# freesoc_sparkfun.net
KiCad netlist of a schematic drawn in EAGLE
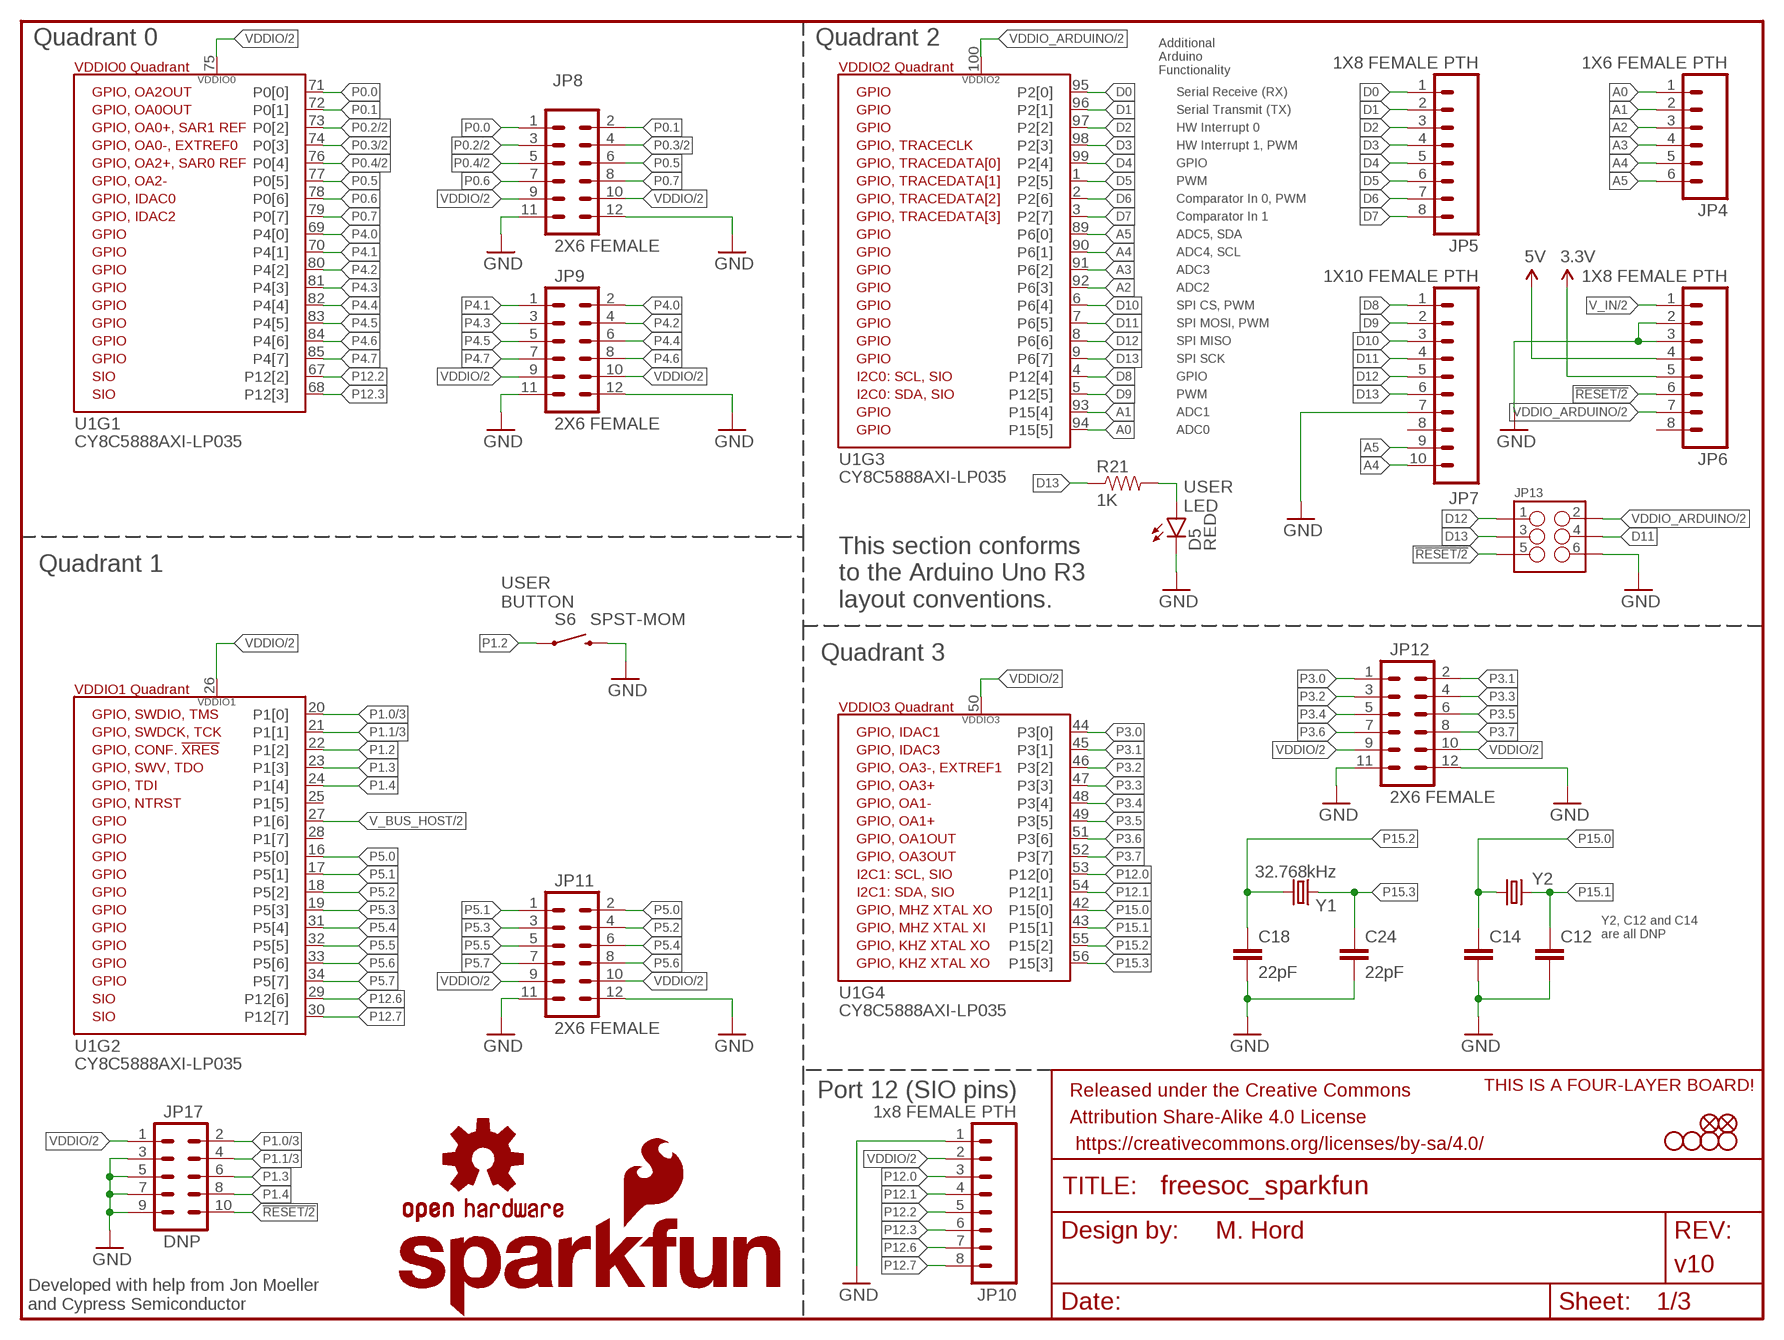
[diagram p0: schematic, sheet 1]
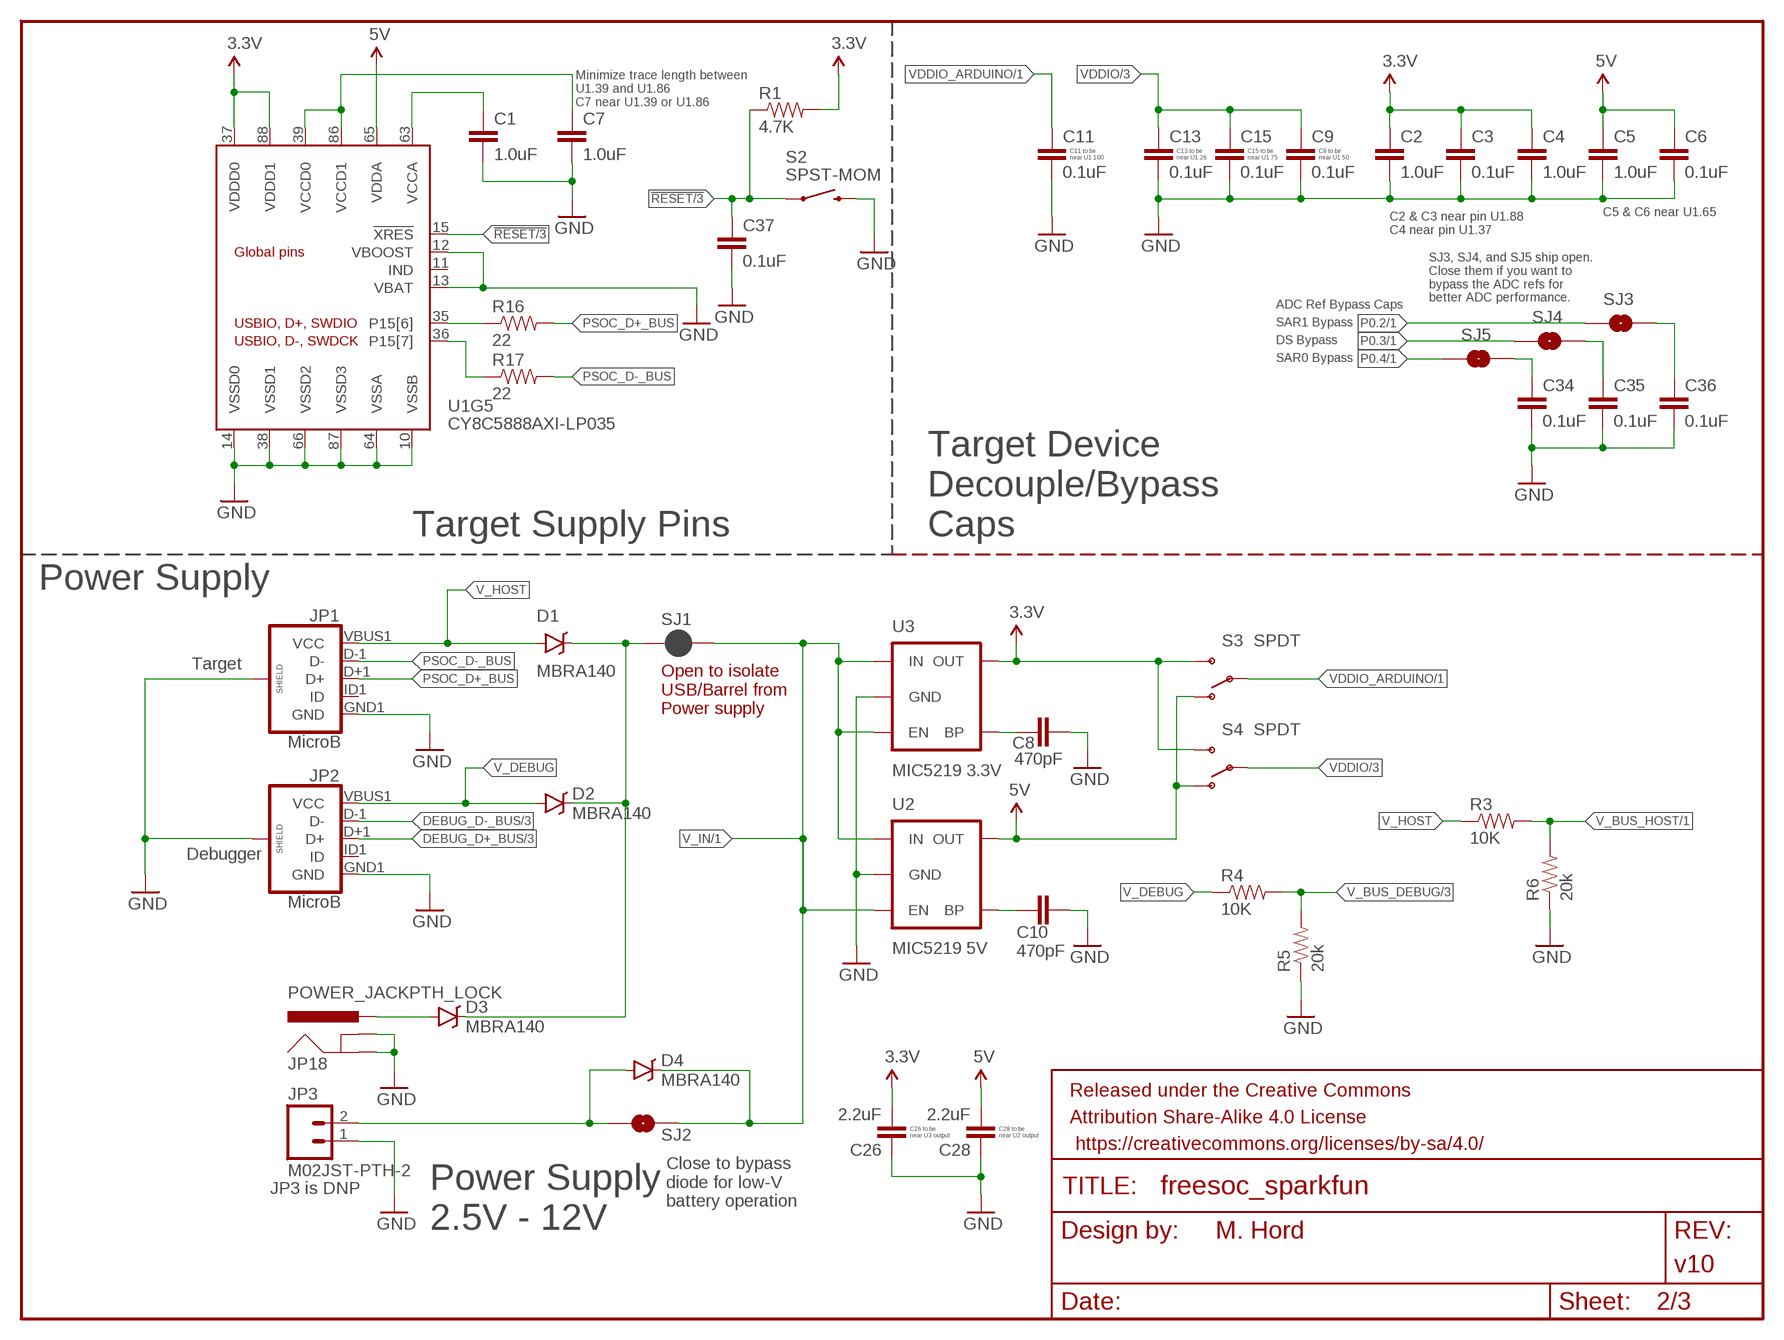
[diagram p1: schematic, sheet 2]
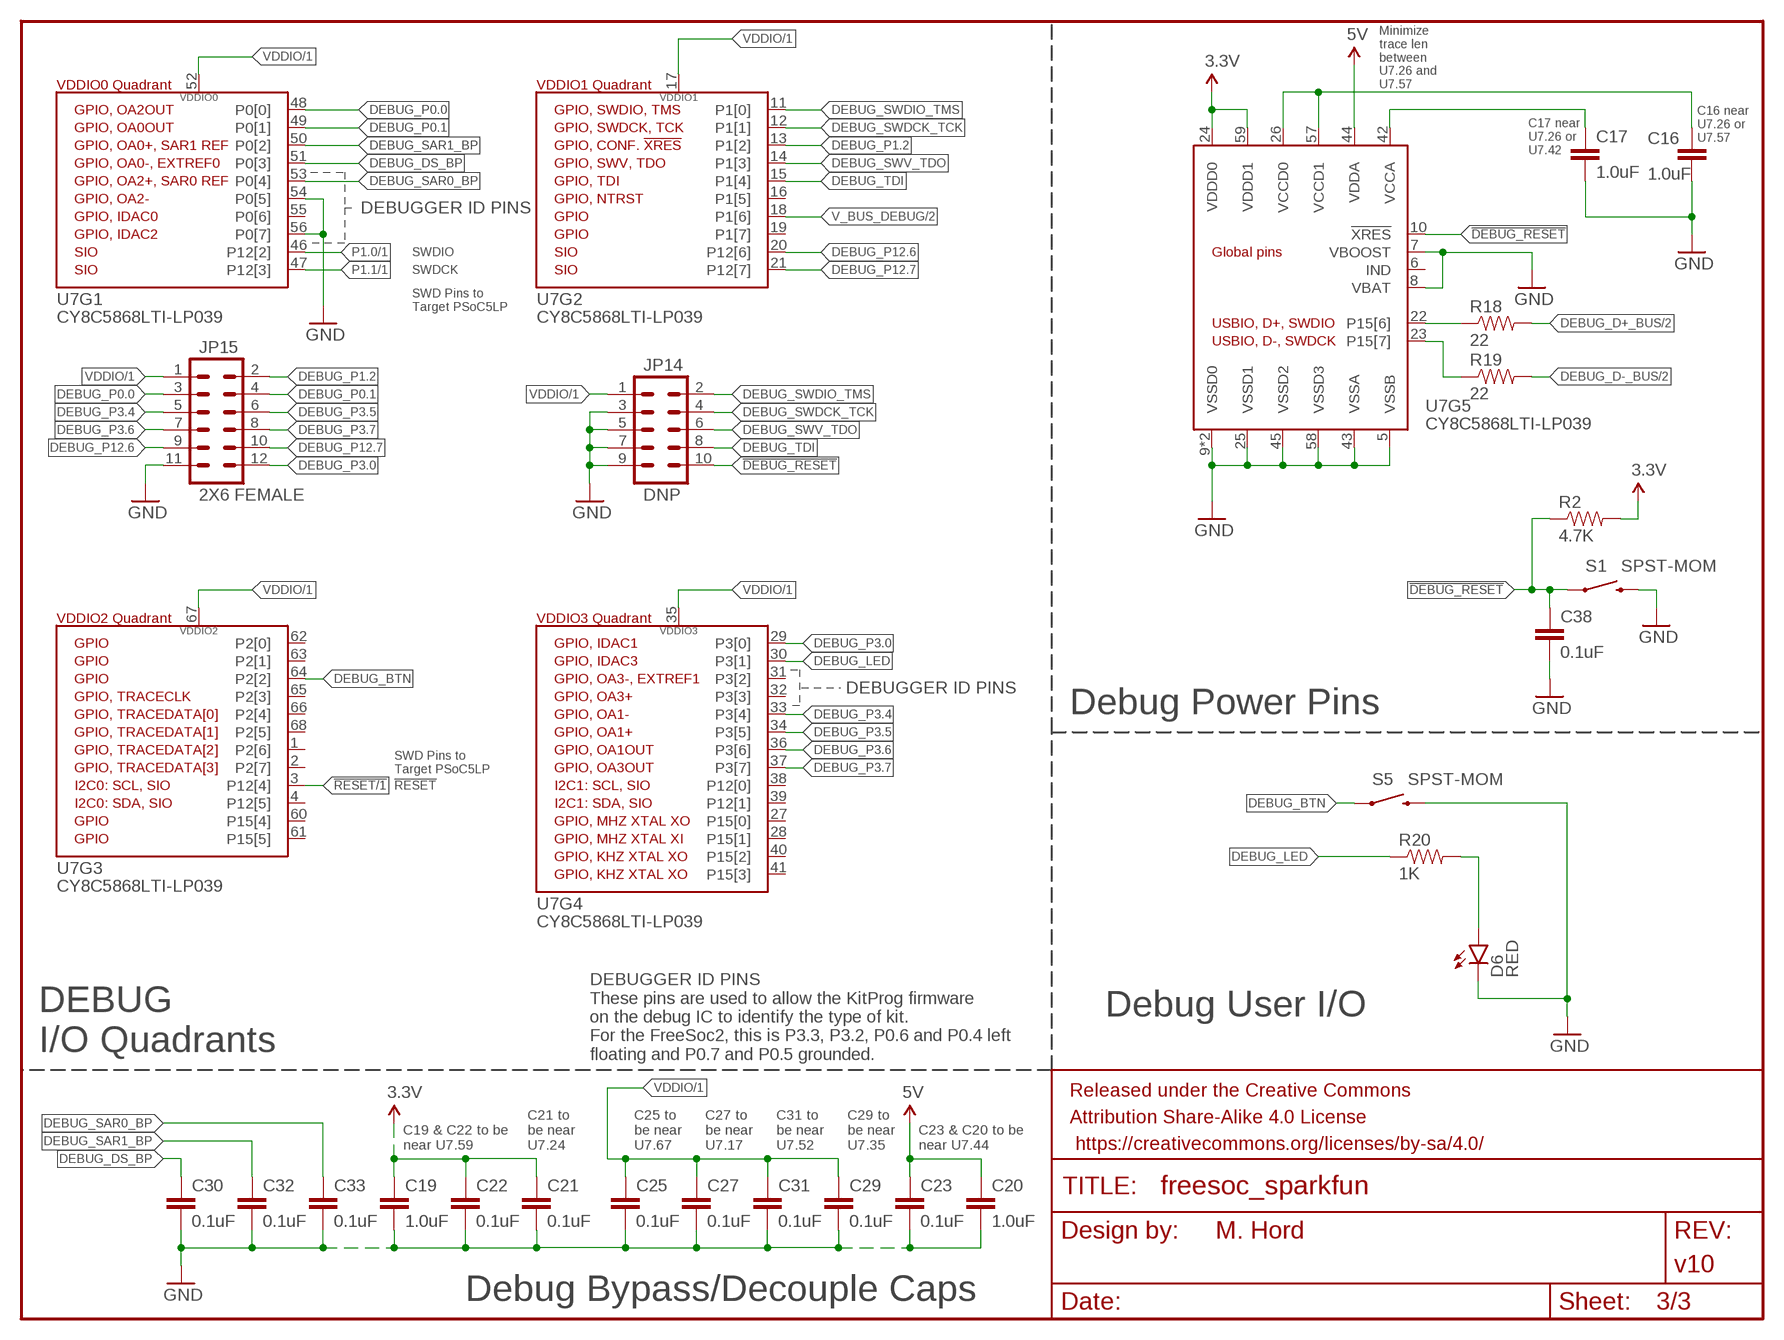
[diagram p2: schematic, sheet 3]

(export (version "E")
  (design (tool "Eeschema 10.0.6"))
  (components
    (comp (ref "C12")
      (value "CAPPTH")
      (footprint "eagle-import:CAP-PTH-SMALL")
      (libsource (lib "eagle-import") (part "CAPPTH"))
    )
    (comp (ref "C14")
      (value "CAPPTH")
      (footprint "eagle-import:CAP-PTH-SMALL")
      (libsource (lib "eagle-import") (part "CAPPTH"))
    )
    (comp (ref "C18")
      (value "22pF")
      (footprint "eagle-import:0603-CAP")
      (libsource (lib "eagle-import") (part "22PF-50V-5%(0603)"))
    )
    (comp (ref "C24")
      (value "22pF")
      (footprint "eagle-import:0603-CAP")
      (libsource (lib "eagle-import") (part "22PF-50V-5%(0603)"))
    )
    (comp (ref "D5")
      (value "RED")
      (footprint "eagle-import:LED-0603")
      (libsource (lib "eagle-import") (part "LED-RED0603"))
    )
    (comp (ref "FID1")
      (value "FIDUCIAL1X2")
      (footprint "eagle-import:FIDUCIAL-1X2")
      (libsource (lib "eagle-import") (part "FIDUCIAL1X2"))
    )
    (comp (ref "FID2")
      (value "FIDUCIAL1X2")
      (footprint "eagle-import:FIDUCIAL-1X2")
      (libsource (lib "eagle-import") (part "FIDUCIAL1X2"))
    )
    (comp (ref "FRAME1")
      (value "FRAME-LETTER")
      (footprint "eagle-import:CREATIVE_COMMONS")
      (fields (field (name "DESIGNER") "M. Hord") (field (name "VERSION") "v10"))
      (libsource (lib "eagle-import") (part "FRAME-LETTER"))
    )
    (comp (ref "JP4")
      (value "1X6 FEMALE PTH")
      (footprint "eagle-import:1X06")
      (libsource (lib "eagle-import") (part "M06SILK_FEMALE_PTH"))
    )
    (comp (ref "JP5")
      (value "1X8 FEMALE PTH")
      (footprint "eagle-import:1X08")
      (libsource (lib "eagle-import") (part "M08SILK_FEMALE_PTH"))
    )
    (comp (ref "JP6")
      (value "1X8 FEMALE PTH")
      (footprint "eagle-import:1X08")
      (libsource (lib "eagle-import") (part "M08SILK_FEMALE_PTH"))
    )
    (comp (ref "JP7")
      (value "1X10 FEMALE PTH")
      (footprint "eagle-import:1X10")
      (libsource (lib "eagle-import") (part "M10SILK_FEMALE_PTH"))
    )
    (comp (ref "JP8")
      (value "2X6 FEMALE")
      (footprint "eagle-import:2X6")
      (libsource (lib "eagle-import") (part "M06X2PTH_FEMALE"))
    )
    (comp (ref "JP9")
      (value "2X6 FEMALE")
      (footprint "eagle-import:2X6")
      (libsource (lib "eagle-import") (part "M06X2PTH_FEMALE"))
    )
    (comp (ref "JP10")
      (value "1x8 FEMALE PTH")
      (footprint "eagle-import:1X08")
      (libsource (lib "eagle-import") (part "M08SILK_FEMALE_PTH"))
    )
    (comp (ref "JP11")
      (value "2X6 FEMALE")
      (footprint "eagle-import:2X6")
      (libsource (lib "eagle-import") (part "M06X2PTH_FEMALE"))
    )
    (comp (ref "JP12")
      (value "2X6 FEMALE")
      (footprint "eagle-import:2X6")
      (libsource (lib "eagle-import") (part "M06X2PTH_FEMALE"))
    )
    (comp (ref "JP13")
      (value "M03X22X3_SILK_MALE_PTH")
      (footprint "eagle-import:2X3")
      (libsource (lib "eagle-import") (part "M03X22X3_SILK_MALE_PTH"))
    )
    (comp (ref "JP17")
      (value "DNP")
      (footprint "eagle-import:2X5_PTH_SILK_.05")
      (libsource (lib "eagle-import") (part "M05X20.05_IN_PTH_SILK"))
    )
    (comp (ref "LOGO1")
      (value "SFE_LOGO_NAME_FLAME.2_INCH")
      (footprint "eagle-import:SFE_LOGO_NAME_FLAME_.2")
      (libsource (lib "eagle-import") (part "SFE_LOGO_NAME_FLAME.2_INCH"))
    )
    (comp (ref "LOGO2")
      (value "OSHW-LOGOS")
      (footprint "eagle-import:OSHW-LOGO-S")
      (libsource (lib "eagle-import") (part "OSHW-LOGOS"))
    )
    (comp (ref "R21")
      (value "1K")
      (footprint "eagle-import:0603-RES")
      (libsource (lib "eagle-import") (part "1KOHM1/10W1%(0603)"))
    )
    (comp (ref "S6")
      (value "SPST-MOM")
      (footprint "eagle-import:TACTILE-SWITCH-SMD")
      (libsource (lib "eagle-import") (part "SWITCH-MOMENTARY-2SMD"))
    )
    (comp (ref "STANDOFF1")
      (value "STAND-OFF")
      (footprint "eagle-import:STAND-OFF")
      (libsource (lib "eagle-import") (part "STAND-OFF"))
    )
    (comp (ref "STANDOFF2")
      (value "STAND-OFF")
      (footprint "eagle-import:STAND-OFF")
      (libsource (lib "eagle-import") (part "STAND-OFF"))
    )
    (comp (ref "STANDOFF3")
      (value "STAND-OFF")
      (footprint "eagle-import:STAND-OFF")
      (libsource (lib "eagle-import") (part "STAND-OFF"))
    )
    (comp (ref "STANDOFF4")
      (value "STAND-OFF")
      (footprint "eagle-import:STAND-OFF")
      (libsource (lib "eagle-import") (part "STAND-OFF"))
    )
    (comp (ref "U$1")
      (value "FOUR_LAYER_WARNING")
      (footprint "eagle-import:FOUR_LAYER_WARNING")
      (libsource (lib "eagle-import") (part "FOUR_LAYER_WARNING"))
    )
    (comp (ref "U1")
      (value "CY8C5888AXI-LP035")
      (footprint "eagle-import:TQFP-100-14X14MM")
      (libsource (lib "eagle-import") (part "PSOC_5LP_100QFP"))
    )
    (comp (ref "Y1")
      (value "32.768kHz")
      (footprint "eagle-import:TC26H")
      (libsource (lib "eagle-import") (part "CRYSTALTC26H"))
    )
    (comp (ref "Y2")
      (value "CRYSTALHC49US")
      (footprint "eagle-import:HC49US")
      (libsource (lib "eagle-import") (part "CRYSTALHC49US"))
    )
    (comp (ref "C16")
      (value "1.0uF")
      (footprint "eagle-import:0402-CAP")
      (libsource (lib "eagle-import") (part "1.0UF-16V-10%(0402)"))
    )
    (comp (ref "C17")
      (value "1.0uF")
      (footprint "eagle-import:0402-CAP")
      (libsource (lib "eagle-import") (part "1.0UF-16V-10%(0402)"))
    )
    (comp (ref "C19")
      (value "1.0uF")
      (footprint "eagle-import:0402-CAP")
      (libsource (lib "eagle-import") (part "1.0UF-16V-10%(0402)"))
    )
    (comp (ref "C20")
      (value "1.0uF")
      (footprint "eagle-import:0402-CAP")
      (libsource (lib "eagle-import") (part "1.0UF-16V-10%(0402)"))
    )
    (comp (ref "C21")
      (value "0.1uF")
      (footprint "eagle-import:0402-CAP")
      (libsource (lib "eagle-import") (part "0.1UF-16V(+-10%)(0402)"))
    )
    (comp (ref "C22")
      (value "0.1uF")
      (footprint "eagle-import:0402-CAP")
      (libsource (lib "eagle-import") (part "0.1UF-16V(+-10%)(0402)"))
    )
    (comp (ref "C23")
      (value "0.1uF")
      (footprint "eagle-import:0402-CAP")
      (libsource (lib "eagle-import") (part "0.1UF-16V(+-10%)(0402)"))
    )
    (comp (ref "C25")
      (value "0.1uF")
      (footprint "eagle-import:0402-CAP")
      (libsource (lib "eagle-import") (part "0.1UF-16V(+-10%)(0402)"))
    )
    (comp (ref "C27")
      (value "0.1uF")
      (footprint "eagle-import:0402-CAP")
      (libsource (lib "eagle-import") (part "0.1UF-16V(+-10%)(0402)"))
    )
    (comp (ref "C29")
      (value "0.1uF")
      (footprint "eagle-import:0402-CAP")
      (libsource (lib "eagle-import") (part "0.1UF-16V(+-10%)(0402)"))
    )
    (comp (ref "C30")
      (value "0.1uF")
      (footprint "eagle-import:0402-CAP")
      (libsource (lib "eagle-import") (part "0.1UF-16V(+-10%)(0402)"))
    )
    (comp (ref "C31")
      (value "0.1uF")
      (footprint "eagle-import:0402-CAP")
      (libsource (lib "eagle-import") (part "0.1UF-16V(+-10%)(0402)"))
    )
    (comp (ref "C32")
      (value "0.1uF")
      (footprint "eagle-import:0402-CAP")
      (libsource (lib "eagle-import") (part "0.1UF-16V(+-10%)(0402)"))
    )
    (comp (ref "C33")
      (value "0.1uF")
      (footprint "eagle-import:0402-CAP")
      (libsource (lib "eagle-import") (part "0.1UF-16V(+-10%)(0402)"))
    )
    (comp (ref "C38")
      (value "0.1uF")
      (footprint "eagle-import:0402-CAP")
      (libsource (lib "eagle-import") (part "0.1UF-16V(+-10%)(0402)"))
    )
    (comp (ref "D6")
      (value "RED")
      (footprint "eagle-import:LED-0603")
      (libsource (lib "eagle-import") (part "LED-RED0603"))
    )
    (comp (ref "FRAME3")
      (value "FRAME-LETTER")
      (footprint "eagle-import:CREATIVE_COMMONS")
      (fields (field (name "DESIGNER") "M. Hord") (field (name "VERSION") "v10"))
      (libsource (lib "eagle-import") (part "FRAME-LETTER"))
    )
    (comp (ref "JP14")
      (value "DNP")
      (footprint "eagle-import:2X5_PTH_SILK_.05")
      (libsource (lib "eagle-import") (part "M05X20.05_IN_PTH_SILK"))
    )
    (comp (ref "JP15")
      (value "2X6 FEMALE")
      (footprint "eagle-import:2X6")
      (libsource (lib "eagle-import") (part "M06X2PTH_FEMALE"))
    )
    (comp (ref "R2")
      (value "4.7K")
      (footprint "eagle-import:0603-RES")
      (libsource (lib "eagle-import") (part "4.7KOHM-1/10W-1%(0603)"))
    )
    (comp (ref "R18")
      (value "22")
      (footprint "eagle-import:0402-RES")
      (libsource (lib "eagle-import") (part "22OHM1/10W1%(0402)"))
    )
    (comp (ref "R19")
      (value "22")
      (footprint "eagle-import:0402-RES")
      (libsource (lib "eagle-import") (part "22OHM1/10W1%(0402)"))
    )
    (comp (ref "R20")
      (value "1K")
      (footprint "eagle-import:0603-RES")
      (libsource (lib "eagle-import") (part "1KOHM1/10W1%(0603)"))
    )
    (comp (ref "S1")
      (value "SPST-MOM")
      (footprint "eagle-import:TACTILE-SWITCH-SMD")
      (libsource (lib "eagle-import") (part "SWITCH-MOMENTARY-2SMD"))
    )
    (comp (ref "S5")
      (value "SPST-MOM")
      (footprint "eagle-import:TACTILE-SWITCH-SMD")
      (libsource (lib "eagle-import") (part "SWITCH-MOMENTARY-2SMD"))
    )
    (comp (ref "U7")
      (value "CY8C5868LTI-LP039")
      (footprint "eagle-import:QFN-68")
      (libsource (lib "eagle-import") (part "PSOC_5LP_68QFN"))
    )
    (comp (ref "C1")
      (value "1.0uF")
      (footprint "eagle-import:0402-CAP")
      (libsource (lib "eagle-import") (part "1.0UF-16V-10%(0402)"))
    )
    (comp (ref "C2")
      (value "1.0uF")
      (footprint "eagle-import:0402-CAP")
      (libsource (lib "eagle-import") (part "1.0UF-16V-10%(0402)"))
    )
    (comp (ref "C3")
      (value "0.1uF")
      (footprint "eagle-import:0402-CAP")
      (libsource (lib "eagle-import") (part "0.1UF-16V(+-10%)(0402)"))
    )
    (comp (ref "C4")
      (value "1.0uF")
      (footprint "eagle-import:0402-CAP")
      (libsource (lib "eagle-import") (part "1.0UF-16V-10%(0402)"))
    )
    (comp (ref "C5")
      (value "1.0uF")
      (footprint "eagle-import:0402-CAP")
      (libsource (lib "eagle-import") (part "1.0UF-16V-10%(0402)"))
    )
    (comp (ref "C6")
      (value "0.1uF")
      (footprint "eagle-import:0402-CAP")
      (libsource (lib "eagle-import") (part "0.1UF-16V(+-10%)(0402)"))
    )
    (comp (ref "C7")
      (value "1.0uF")
      (footprint "eagle-import:0402-CAP")
      (libsource (lib "eagle-import") (part "1.0UF-16V-10%(0402)"))
    )
    (comp (ref "C8")
      (value "470pF")
      (footprint "eagle-import:0603-CAP")
      (libsource (lib "eagle-import") (part "470PF-50V-5%(0603)SMD"))
    )
    (comp (ref "C9")
      (value "0.1uF")
      (footprint "eagle-import:0402-CAP")
      (libsource (lib "eagle-import") (part "0.1UF-16V(+-10%)(0402)"))
    )
    (comp (ref "C10")
      (value "470pF")
      (footprint "eagle-import:0603-CAP")
      (libsource (lib "eagle-import") (part "470PF-50V-5%(0603)SMD"))
    )
    (comp (ref "C11")
      (value "0.1uF")
      (footprint "eagle-import:0402-CAP")
      (libsource (lib "eagle-import") (part "0.1UF-16V(+-10%)(0402)"))
    )
    (comp (ref "C13")
      (value "0.1uF")
      (footprint "eagle-import:0402-CAP")
      (libsource (lib "eagle-import") (part "0.1UF-16V(+-10%)(0402)"))
    )
    (comp (ref "C15")
      (value "0.1uF")
      (footprint "eagle-import:0402-CAP")
      (libsource (lib "eagle-import") (part "0.1UF-16V(+-10%)(0402)"))
    )
    (comp (ref "C26")
      (value "2.2uF")
      (footprint "eagle-import:0603-CAP")
      (libsource (lib "eagle-import") (part "2.2UF-10V-20%(0603)"))
    )
    (comp (ref "C28")
      (value "2.2uF")
      (footprint "eagle-import:0603-CAP")
      (libsource (lib "eagle-import") (part "2.2UF-10V-20%(0603)"))
    )
    (comp (ref "C34")
      (value "0.1uF")
      (footprint "eagle-import:0402-CAP")
      (libsource (lib "eagle-import") (part "0.1UF-16V(+-10%)(0402)"))
    )
    (comp (ref "C35")
      (value "0.1uF")
      (footprint "eagle-import:0402-CAP")
      (libsource (lib "eagle-import") (part "0.1UF-16V(+-10%)(0402)"))
    )
    (comp (ref "C36")
      (value "0.1uF")
      (footprint "eagle-import:0402-CAP")
      (libsource (lib "eagle-import") (part "0.1UF-16V(+-10%)(0402)"))
    )
    (comp (ref "C37")
      (value "0.1uF")
      (footprint "eagle-import:0402-CAP")
      (libsource (lib "eagle-import") (part "0.1UF-16V(+-10%)(0402)"))
    )
    (comp (ref "D1")
      (value "MBRA140")
      (footprint "eagle-import:SMA-DIODE")
      (libsource (lib "eagle-import") (part "MBRA140"))
    )
    (comp (ref "D2")
      (value "MBRA140")
      (footprint "eagle-import:SMA-DIODE")
      (libsource (lib "eagle-import") (part "MBRA140"))
    )
    (comp (ref "D3")
      (value "MBRA140")
      (footprint "eagle-import:SMA-DIODE")
      (libsource (lib "eagle-import") (part "MBRA140"))
    )
    (comp (ref "D4")
      (value "MBRA140")
      (footprint "eagle-import:SMA-DIODE")
      (libsource (lib "eagle-import") (part "MBRA140"))
    )
    (comp (ref "FRAME2")
      (value "FRAME-LETTER")
      (footprint "eagle-import:CREATIVE_COMMONS")
      (fields (field (name "DESIGNER") "M. Hord") (field (name "VERSION") "v10"))
      (libsource (lib "eagle-import") (part "FRAME-LETTER"))
    )
    (comp (ref "JP1")
      (value "MicroB")
      (footprint "eagle-import:USB-B-MICRO-SMD_V03")
      (libsource (lib "eagle-import") (part "USB_MICROB_PLUGCONN-11752"))
    )
    (comp (ref "JP2")
      (value "MicroB")
      (footprint "eagle-import:USB-B-MICRO-SMD_V03")
      (libsource (lib "eagle-import") (part "USB_MICROB_PLUGCONN-11752"))
    )
    (comp (ref "JP3")
      (value "M02JST-PTH-2")
      (footprint "eagle-import:JST-2-PTH")
      (libsource (lib "eagle-import") (part "M02JST-PTH-2"))
    )
    (comp (ref "JP18")
      (value "POWER_JACKPTH_LOCK")
      (footprint "eagle-import:POWER_JACK_PTH_LOCK")
      (libsource (lib "eagle-import") (part "POWER_JACKPTH_LOCK"))
    )
    (comp (ref "R1")
      (value "4.7K")
      (footprint "eagle-import:0603-RES")
      (libsource (lib "eagle-import") (part "4.7KOHM-1/10W-1%(0603)"))
    )
    (comp (ref "R3")
      (value "10K")
      (footprint "eagle-import:0603-RES")
      (libsource (lib "eagle-import") (part "10KOHM-1/10W-1%(0603)0603"))
    )
    (comp (ref "R4")
      (value "10K")
      (footprint "eagle-import:0603-RES")
      (libsource (lib "eagle-import") (part "10KOHM-1/10W-1%(0603)0603"))
    )
    (comp (ref "R5")
      (value "20k")
      (footprint "eagle-import:0603-RES")
      (libsource (lib "eagle-import") (part "20KOHM1/10W1%(0603)"))
    )
    (comp (ref "R6")
      (value "20k")
      (footprint "eagle-import:0603-RES")
      (libsource (lib "eagle-import") (part "20KOHM1/10W1%(0603)"))
    )
    (comp (ref "R16")
      (value "22")
      (footprint "eagle-import:0402-RES")
      (libsource (lib "eagle-import") (part "22OHM1/10W1%(0402)"))
    )
    (comp (ref "R17")
      (value "22")
      (footprint "eagle-import:0402-RES")
      (libsource (lib "eagle-import") (part "22OHM1/10W1%(0402)"))
    )
    (comp (ref "S2")
      (value "SPST-MOM")
      (footprint "eagle-import:TACTILE-SWITCH-SMD")
      (libsource (lib "eagle-import") (part "SWITCH-MOMENTARY-2SMD"))
    )
    (comp (ref "S3")
      (value "SPDT")
      (footprint "eagle-import:SWITCH-SPDT_LOCK.007S")
      (libsource (lib "eagle-import") (part "SWITCH-SPDTPTH_LOCK"))
    )
    (comp (ref "S4")
      (value "SPDT")
      (footprint "eagle-import:SWITCH-SPDT_LOCK.007S")
      (libsource (lib "eagle-import") (part "SWITCH-SPDTPTH_LOCK"))
    )
    (comp (ref "SJ1")
      (value "JUMPER-PAD-2-NC_BY_PASTE")
      (footprint "eagle-import:PAD-JUMPER-2-NC_BY_PASTE_YES_SILK")
      (libsource (lib "eagle-import") (part "JUMPER-PAD-2-NC_BY_PASTE"))
    )
    (comp (ref "SJ2")
      (value "JUMPER-PAD-2-NOYES_SILK")
      (footprint "eagle-import:PAD-JUMPER-2-NO_YES_SILK")
      (libsource (lib "eagle-import") (part "JUMPER-PAD-2-NOYES_SILK"))
    )
    (comp (ref "SJ3")
      (value "JUMPER-PAD-2-NO")
      (footprint "eagle-import:PAD-JUMPER-2-NO_NO_SILK")
      (libsource (lib "eagle-import") (part "JUMPER-PAD-2-NO"))
    )
    (comp (ref "SJ4")
      (value "JUMPER-PAD-2-NO")
      (footprint "eagle-import:PAD-JUMPER-2-NO_NO_SILK")
      (libsource (lib "eagle-import") (part "JUMPER-PAD-2-NO"))
    )
    (comp (ref "SJ5")
      (value "JUMPER-PAD-2-NO")
      (footprint "eagle-import:PAD-JUMPER-2-NO_NO_SILK")
      (libsource (lib "eagle-import") (part "JUMPER-PAD-2-NO"))
    )
    (comp (ref "U2")
      (value "MIC5219 5V")
      (footprint "eagle-import:SOT23-5")
      (libsource (lib "eagle-import") (part "V_REG_MIC52195V"))
    )
    (comp (ref "U3")
      (value "MIC5219 3.3V")
      (footprint "eagle-import:SOT23-5")
      (libsource (lib "eagle-import") (part "V_REG_MIC52193.3V"))
    )
  )
  (nets
    (net (code "1") (name "3.3V") (class "Default")
      (node (ref "C19") (pin "1") (pinfunction "1_1") (pintype "passive"))
      (node (ref "C2") (pin "1") (pinfunction "1_1") (pintype "passive"))
      (node (ref "C21") (pin "1") (pinfunction "1_1") (pintype "passive"))
      (node (ref "C22") (pin "1") (pinfunction "1_1") (pintype "passive"))
      (node (ref "C26") (pin "2") (pinfunction "2_2") (pintype "passive"))
      (node (ref "C3") (pin "1") (pinfunction "1_1") (pintype "passive"))
      (node (ref "C4") (pin "1") (pinfunction "1_1") (pintype "passive"))
      (node (ref "JP6") (pin "5") (pinfunction "5_5") (pintype "passive"))
      (node (ref "R1") (pin "2") (pinfunction "2_2") (pintype "passive"))
      (node (ref "R2") (pin "2") (pinfunction "2_2") (pintype "passive"))
      (node (ref "S3") (pin "3") (pinfunction "S_3") (pintype "passive"))
      (node (ref "S4") (pin "3") (pinfunction "S_3") (pintype "passive"))
      (node (ref "U1") (pin "37") (pinfunction "VDDD0_37") (pintype "bidirectional"))
      (node (ref "U1") (pin "88") (pinfunction "VDDD1_88") (pintype "bidirectional"))
      (node (ref "U3") (pin "5") (pinfunction "OUT_5") (pintype "passive"))
      (node (ref "U7") (pin "24") (pinfunction "VDDD0_24") (pintype "bidirectional"))
      (node (ref "U7") (pin "59") (pinfunction "VDDD1_59") (pintype "bidirectional"))
    )
    (net (code "2") (name "5V") (class "Default")
      (node (ref "C20") (pin "1") (pinfunction "1_1") (pintype "passive"))
      (node (ref "C23") (pin "1") (pinfunction "1_1") (pintype "passive"))
      (node (ref "C28") (pin "2") (pinfunction "2_2") (pintype "passive"))
      (node (ref "C5") (pin "1") (pinfunction "1_1") (pintype "passive"))
      (node (ref "C6") (pin "1") (pinfunction "1_1") (pintype "passive"))
      (node (ref "JP6") (pin "4") (pinfunction "4_4") (pintype "passive"))
      (node (ref "S3") (pin "1") (pinfunction "O_1") (pintype "passive"))
      (node (ref "S4") (pin "1") (pinfunction "O_1") (pintype "passive"))
      (node (ref "U1") (pin "65") (pinfunction "VDDA_65") (pintype "bidirectional"))
      (node (ref "U2") (pin "5") (pinfunction "OUT_5") (pintype "passive"))
      (node (ref "U7") (pin "44") (pinfunction "VDDA_44") (pintype "bidirectional"))
    )
    (net (code "3") (name "A0") (class "Default")
      (node (ref "JP4") (pin "1") (pinfunction "1_1") (pintype "passive"))
      (node (ref "U1") (pin "94") (pinfunction "P15[5]_94") (pintype "bidirectional"))
    )
    (net (code "4") (name "A1") (class "Default")
      (node (ref "JP4") (pin "2") (pinfunction "2_2") (pintype "passive"))
      (node (ref "U1") (pin "93") (pinfunction "P15[4]_93") (pintype "bidirectional"))
    )
    (net (code "5") (name "A2") (class "Default")
      (node (ref "JP4") (pin "3") (pinfunction "3_3") (pintype "passive"))
      (node (ref "U1") (pin "92") (pinfunction "P6[3]_92") (pintype "bidirectional"))
    )
    (net (code "6") (name "A3") (class "Default")
      (node (ref "JP4") (pin "4") (pinfunction "4_4") (pintype "passive"))
      (node (ref "U1") (pin "91") (pinfunction "P6[2]_91") (pintype "bidirectional"))
    )
    (net (code "7") (name "A4") (class "Default")
      (node (ref "JP4") (pin "5") (pinfunction "5_5") (pintype "passive"))
      (node (ref "JP7") (pin "10") (pinfunction "10_10") (pintype "passive"))
      (node (ref "U1") (pin "90") (pinfunction "P6[1]_90") (pintype "bidirectional"))
    )
    (net (code "8") (name "A5") (class "Default")
      (node (ref "JP4") (pin "6") (pinfunction "6_6") (pintype "passive"))
      (node (ref "JP7") (pin "9") (pinfunction "9_9") (pintype "passive"))
      (node (ref "U1") (pin "89") (pinfunction "P6[0]_89") (pintype "bidirectional"))
    )
    (net (code "9") (name "D0") (class "Default")
      (node (ref "JP5") (pin "1") (pinfunction "1_1") (pintype "passive"))
      (node (ref "U1") (pin "95") (pinfunction "P2[0]_95") (pintype "bidirectional"))
    )
    (net (code "10") (name "D1") (class "Default")
      (node (ref "JP5") (pin "2") (pinfunction "2_2") (pintype "passive"))
      (node (ref "U1") (pin "96") (pinfunction "P2[1]_96") (pintype "bidirectional"))
    )
    (net (code "11") (name "D2") (class "Default")
      (node (ref "JP5") (pin "3") (pinfunction "3_3") (pintype "passive"))
      (node (ref "U1") (pin "97") (pinfunction "P2[2]_97") (pintype "bidirectional"))
    )
    (net (code "12") (name "D3") (class "Default")
      (node (ref "JP5") (pin "4") (pinfunction "4_4") (pintype "passive"))
      (node (ref "U1") (pin "98") (pinfunction "P2[3]_98") (pintype "bidirectional"))
    )
    (net (code "13") (name "D4") (class "Default")
      (node (ref "JP5") (pin "5") (pinfunction "5_5") (pintype "passive"))
      (node (ref "U1") (pin "99") (pinfunction "P2[4]_99") (pintype "bidirectional"))
    )
    (net (code "14") (name "D5") (class "Default")
      (node (ref "JP5") (pin "6") (pinfunction "6_6") (pintype "passive"))
      (node (ref "U1") (pin "1") (pinfunction "P2[5]_1") (pintype "bidirectional"))
    )
    (net (code "15") (name "D6") (class "Default")
      (node (ref "JP5") (pin "7") (pinfunction "7_7") (pintype "passive"))
      (node (ref "U1") (pin "2") (pinfunction "P2[6]_2") (pintype "bidirectional"))
    )
    (net (code "16") (name "D7") (class "Default")
      (node (ref "JP5") (pin "8") (pinfunction "8_8") (pintype "passive"))
      (node (ref "U1") (pin "3") (pinfunction "P2[7]_3") (pintype "bidirectional"))
    )
    (net (code "17") (name "D8") (class "Default")
      (node (ref "JP7") (pin "1") (pinfunction "1_1") (pintype "passive"))
      (node (ref "U1") (pin "4") (pinfunction "P12[4]_4") (pintype "bidirectional"))
    )
    (net (code "18") (name "D9") (class "Default")
      (node (ref "JP7") (pin "2") (pinfunction "2_2") (pintype "passive"))
      (node (ref "U1") (pin "5") (pinfunction "P12[5]_5") (pintype "bidirectional"))
    )
    (net (code "19") (name "D10") (class "Default")
      (node (ref "JP7") (pin "3") (pinfunction "3_3") (pintype "passive"))
      (node (ref "U1") (pin "6") (pinfunction "P6[4]_6") (pintype "bidirectional"))
    )
    (net (code "20") (name "D11") (class "Default")
      (node (ref "JP13") (pin "4") (pinfunction "4_4") (pintype "bidirectional"))
      (node (ref "JP7") (pin "4") (pinfunction "4_4") (pintype "passive"))
      (node (ref "U1") (pin "7") (pinfunction "P6[5]_7") (pintype "bidirectional"))
    )
    (net (code "21") (name "D12") (class "Default")
      (node (ref "JP13") (pin "1") (pinfunction "1_1") (pintype "bidirectional"))
      (node (ref "JP7") (pin "5") (pinfunction "5_5") (pintype "passive"))
      (node (ref "U1") (pin "8") (pinfunction "P6[6]_8") (pintype "bidirectional"))
    )
    (net (code "22") (name "D13") (class "Default")
      (node (ref "JP13") (pin "3") (pinfunction "3_3") (pintype "bidirectional"))
      (node (ref "JP7") (pin "6") (pinfunction "6_6") (pintype "passive"))
      (node (ref "R21") (pin "1") (pinfunction "1_1") (pintype "passive"))
      (node (ref "U1") (pin "9") (pinfunction "P6[7]_9") (pintype "bidirectional"))
    )
    (net (code "23") (name "DEBUG_BTN") (class "Default")
      (node (ref "S5") (pin "1") (pinfunction "1_1") (pintype "passive"))
      (node (ref "U7") (pin "64") (pinfunction "P2[2]_64") (pintype "bidirectional"))
    )
    (net (code "24") (name "DEBUG_D+_BUS") (class "Default")
      (node (ref "JP2") (pin "D+1") (pinfunction "D+_D+1") (pintype "bidirectional"))
      (node (ref "R18") (pin "2") (pinfunction "2_2") (pintype "passive"))
    )
    (net (code "25") (name "DEBUG_D-_BUS") (class "Default")
      (node (ref "JP2") (pin "D-1") (pinfunction "D-_D-1") (pintype "bidirectional"))
      (node (ref "R19") (pin "2") (pinfunction "2_2") (pintype "passive"))
    )
    (net (code "26") (name "DEBUG_DS_BP") (class "Default")
      (node (ref "C30") (pin "1") (pinfunction "1_1") (pintype "passive"))
      (node (ref "U7") (pin "51") (pinfunction "P0[3]_51") (pintype "bidirectional"))
    )
    (net (code "27") (name "DEBUG_LED") (class "Default")
      (node (ref "R20") (pin "1") (pinfunction "1_1") (pintype "passive"))
      (node (ref "U7") (pin "30") (pinfunction "P3[1]_30") (pintype "bidirectional"))
    )
    (net (code "28") (name "DEBUG_P0.0") (class "Default")
      (node (ref "JP15") (pin "3") (pinfunction "3_3") (pintype "passive"))
      (node (ref "U7") (pin "48") (pinfunction "P0[0]_48") (pintype "bidirectional"))
    )
    (net (code "29") (name "DEBUG_P0.1") (class "Default")
      (node (ref "JP15") (pin "4") (pinfunction "4_4") (pintype "passive"))
      (node (ref "U7") (pin "49") (pinfunction "P0[1]_49") (pintype "bidirectional"))
    )
    (net (code "30") (name "DEBUG_P1.2") (class "Default")
      (node (ref "JP15") (pin "2") (pinfunction "2_2") (pintype "passive"))
      (node (ref "U7") (pin "13") (pinfunction "P1[2]_13") (pintype "bidirectional"))
    )
    (net (code "31") (name "DEBUG_P3.0") (class "Default")
      (node (ref "JP15") (pin "12") (pinfunction "12_12") (pintype "passive"))
      (node (ref "U7") (pin "29") (pinfunction "P3[0]_29") (pintype "bidirectional"))
    )
    (net (code "32") (name "DEBUG_P3.4") (class "Default")
      (node (ref "JP15") (pin "5") (pinfunction "5_5") (pintype "passive"))
      (node (ref "U7") (pin "33") (pinfunction "P3[4]_33") (pintype "bidirectional"))
    )
    (net (code "33") (name "DEBUG_P3.5") (class "Default")
      (node (ref "JP15") (pin "6") (pinfunction "6_6") (pintype "passive"))
      (node (ref "U7") (pin "34") (pinfunction "P3[5]_34") (pintype "bidirectional"))
    )
    (net (code "34") (name "DEBUG_P3.6") (class "Default")
      (node (ref "JP15") (pin "7") (pinfunction "7_7") (pintype "passive"))
      (node (ref "U7") (pin "36") (pinfunction "P3[6]_36") (pintype "bidirectional"))
    )
    (net (code "35") (name "DEBUG_P3.7") (class "Default")
      (node (ref "JP15") (pin "8") (pinfunction "8_8") (pintype "passive"))
      (node (ref "U7") (pin "37") (pinfunction "P3[7]_37") (pintype "bidirectional"))
    )
    (net (code "36") (name "DEBUG_P12.6") (class "Default")
      (node (ref "JP15") (pin "9") (pinfunction "9_9") (pintype "passive"))
      (node (ref "U7") (pin "20") (pinfunction "P12[6]_20") (pintype "bidirectional"))
    )
    (net (code "37") (name "DEBUG_P12.7") (class "Default")
      (node (ref "JP15") (pin "10") (pinfunction "10_10") (pintype "passive"))
      (node (ref "U7") (pin "21") (pinfunction "P12[7]_21") (pintype "bidirectional"))
    )
    (net (code "38") (name "DEBUG_SAR0_BP") (class "Default")
      (node (ref "C33") (pin "1") (pinfunction "1_1") (pintype "passive"))
      (node (ref "U7") (pin "53") (pinfunction "P0[4]_53") (pintype "bidirectional"))
    )
    (net (code "39") (name "DEBUG_SAR1_BP") (class "Default")
      (node (ref "C32") (pin "1") (pinfunction "1_1") (pintype "passive"))
      (node (ref "U7") (pin "50") (pinfunction "P0[2]_50") (pintype "bidirectional"))
    )
    (net (code "40") (name "DEBUG_SWDCK_TCK") (class "Default")
      (node (ref "JP14") (pin "4") (pinfunction "4_4") (pintype "passive"))
      (node (ref "U7") (pin "12") (pinfunction "P1[1]_12") (pintype "bidirectional"))
    )
    (net (code "41") (name "DEBUG_SWDIO_TMS") (class "Default")
      (node (ref "JP14") (pin "2") (pinfunction "2_2") (pintype "passive"))
      (node (ref "U7") (pin "11") (pinfunction "P1[0]_11") (pintype "bidirectional"))
    )
    (net (code "42") (name "DEBUG_SWV_TDO") (class "Default")
      (node (ref "JP14") (pin "6") (pinfunction "6_6") (pintype "passive"))
      (node (ref "U7") (pin "14") (pinfunction "P1[3]_14") (pintype "bidirectional"))
    )
    (net (code "43") (name "DEBUG_TDI") (class "Default")
      (node (ref "JP14") (pin "8") (pinfunction "8_8") (pintype "passive"))
      (node (ref "U7") (pin "15") (pinfunction "P1[4]_15") (pintype "bidirectional"))
    )
    (net (code "44") (name "GND") (class "Default")
      (node (ref "C1") (pin "2") (pinfunction "2_2") (pintype "passive"))
      (node (ref "C10") (pin "2") (pinfunction "2_2") (pintype "passive"))
      (node (ref "C11") (pin "2") (pinfunction "2_2") (pintype "passive"))
      (node (ref "C12") (pin "2") (pinfunction "2_2") (pintype "passive"))
      (node (ref "C13") (pin "2") (pinfunction "2_2") (pintype "passive"))
      (node (ref "C14") (pin "2") (pinfunction "2_2") (pintype "passive"))
      (node (ref "C15") (pin "2") (pinfunction "2_2") (pintype "passive"))
      (node (ref "C16") (pin "2") (pinfunction "2_2") (pintype "passive"))
      (node (ref "C17") (pin "2") (pinfunction "2_2") (pintype "passive"))
      (node (ref "C18") (pin "2") (pinfunction "2_2") (pintype "passive"))
      (node (ref "C19") (pin "2") (pinfunction "2_2") (pintype "passive"))
      (node (ref "C2") (pin "2") (pinfunction "2_2") (pintype "passive"))
      (node (ref "C20") (pin "2") (pinfunction "2_2") (pintype "passive"))
      (node (ref "C21") (pin "2") (pinfunction "2_2") (pintype "passive"))
      (node (ref "C22") (pin "2") (pinfunction "2_2") (pintype "passive"))
      (node (ref "C23") (pin "2") (pinfunction "2_2") (pintype "passive"))
      (node (ref "C24") (pin "2") (pinfunction "2_2") (pintype "passive"))
      (node (ref "C25") (pin "2") (pinfunction "2_2") (pintype "passive"))
      (node (ref "C26") (pin "1") (pinfunction "1_1") (pintype "passive"))
      (node (ref "C27") (pin "2") (pinfunction "2_2") (pintype "passive"))
      (node (ref "C28") (pin "1") (pinfunction "1_1") (pintype "passive"))
      (node (ref "C29") (pin "2") (pinfunction "2_2") (pintype "passive"))
      (node (ref "C3") (pin "2") (pinfunction "2_2") (pintype "passive"))
      (node (ref "C30") (pin "2") (pinfunction "2_2") (pintype "passive"))
      (node (ref "C31") (pin "2") (pinfunction "2_2") (pintype "passive"))
      (node (ref "C32") (pin "2") (pinfunction "2_2") (pintype "passive"))
      (node (ref "C33") (pin "2") (pinfunction "2_2") (pintype "passive"))
      (node (ref "C34") (pin "2") (pinfunction "2_2") (pintype "passive"))
      (node (ref "C35") (pin "2") (pinfunction "2_2") (pintype "passive"))
      (node (ref "C36") (pin "2") (pinfunction "2_2") (pintype "passive"))
      (node (ref "C37") (pin "2") (pinfunction "2_2") (pintype "passive"))
      (node (ref "C38") (pin "2") (pinfunction "2_2") (pintype "passive"))
      (node (ref "C4") (pin "2") (pinfunction "2_2") (pintype "passive"))
      (node (ref "C5") (pin "2") (pinfunction "2_2") (pintype "passive"))
      (node (ref "C6") (pin "2") (pinfunction "2_2") (pintype "passive"))
      (node (ref "C7") (pin "2") (pinfunction "2_2") (pintype "passive"))
      (node (ref "C8") (pin "2") (pinfunction "2_2") (pintype "passive"))
      (node (ref "C9") (pin "2") (pinfunction "2_2") (pintype "passive"))
      (node (ref "D5") (pin "C") (pinfunction "C_C") (pintype "passive"))
      (node (ref "D6") (pin "C") (pinfunction "C_C") (pintype "passive"))
      (node (ref "JP1") (pin "GND1") (pinfunction "GND_GND1") (pintype "bidirectional"))
      (node (ref "JP1") (pin "SHIELD1") (pinfunction "SHIELD_SHIELD1") (pintype "bidirectional"))
      (node (ref "JP1") (pin "SHIELD2") (pinfunction "SHIELD_SHIELD2") (pintype "bidirectional"))
      (node (ref "JP1") (pin "SHIELD3") (pinfunction "SHIELD_SHIELD3") (pintype "bidirectional"))
      (node (ref "JP10") (pin "1") (pinfunction "1_1") (pintype "passive"))
      (node (ref "JP11") (pin "11") (pinfunction "11_11") (pintype "passive"))
      (node (ref "JP11") (pin "12") (pinfunction "12_12") (pintype "passive"))
      (node (ref "JP12") (pin "11") (pinfunction "11_11") (pintype "passive"))
      (node (ref "JP12") (pin "12") (pinfunction "12_12") (pintype "passive"))
      (node (ref "JP13") (pin "6") (pinfunction "6_6") (pintype "bidirectional"))
      (node (ref "JP14") (pin "3") (pinfunction "3_3") (pintype "passive"))
      (node (ref "JP14") (pin "5") (pinfunction "5_5") (pintype "passive"))
      (node (ref "JP14") (pin "7") (pinfunction "7_7") (pintype "passive"))
      (node (ref "JP14") (pin "9") (pinfunction "9_9") (pintype "passive"))
      (node (ref "JP15") (pin "11") (pinfunction "11_11") (pintype "passive"))
      (node (ref "JP17") (pin "3") (pinfunction "3_3") (pintype "passive"))
      (node (ref "JP17") (pin "5") (pinfunction "5_5") (pintype "passive"))
      (node (ref "JP17") (pin "7") (pinfunction "7_7") (pintype "passive"))
      (node (ref "JP17") (pin "9") (pinfunction "9_9") (pintype "passive"))
      (node (ref "JP18") (pin "GND") (pinfunction "GND_GND") (pintype "bidirectional"))
      (node (ref "JP18") (pin "GNDBREAK") (pinfunction "GNDBREAK_GNDBREAK") (pintype "bidirectional"))
      (node (ref "JP2") (pin "GND1") (pinfunction "GND_GND1") (pintype "bidirectional"))
      (node (ref "JP2") (pin "SHIELD1") (pinfunction "SHIELD_SHIELD1") (pintype "bidirectional"))
      (node (ref "JP2") (pin "SHIELD2") (pinfunction "SHIELD_SHIELD2") (pintype "bidirectional"))
      (node (ref "JP2") (pin "SHIELD3") (pinfunction "SHIELD_SHIELD3") (pintype "bidirectional"))
      (node (ref "JP3") (pin "1") (pinfunction "1_1") (pintype "passive"))
      (node (ref "JP6") (pin "2") (pinfunction "2_2") (pintype "passive"))
      (node (ref "JP6") (pin "3") (pinfunction "3_3") (pintype "passive"))
      (node (ref "JP7") (pin "7") (pinfunction "7_7") (pintype "passive"))
      (node (ref "JP8") (pin "11") (pinfunction "11_11") (pintype "passive"))
      (node (ref "JP8") (pin "12") (pinfunction "12_12") (pintype "passive"))
      (node (ref "JP9") (pin "11") (pinfunction "11_11") (pintype "passive"))
      (node (ref "JP9") (pin "12") (pinfunction "12_12") (pintype "passive"))
      (node (ref "R5") (pin "1") (pinfunction "1_1") (pintype "passive"))
      (node (ref "R6") (pin "1") (pinfunction "1_1") (pintype "passive"))
      (node (ref "S1") (pin "3") (pinfunction "2_3") (pintype "passive"))
      (node (ref "S2") (pin "3") (pinfunction "2_3") (pintype "passive"))
      (node (ref "S5") (pin "3") (pinfunction "2_3") (pintype "passive"))
      (node (ref "S6") (pin "3") (pinfunction "2_3") (pintype "passive"))
      (node (ref "U1") (pin "10") (pinfunction "VSSB_10") (pintype "bidirectional"))
      (node (ref "U1") (pin "12") (pinfunction "VBOOST_12") (pintype "bidirectional"))
      (node (ref "U1") (pin "13") (pinfunction "VBAT_13") (pintype "bidirectional"))
      (node (ref "U1") (pin "14") (pinfunction "VSSD0_14") (pintype "bidirectional"))
      (node (ref "U1") (pin "38") (pinfunction "VSSD1_38") (pintype "bidirectional"))
      (node (ref "U1") (pin "64") (pinfunction "VSSA_64") (pintype "bidirectional"))
      (node (ref "U1") (pin "66") (pinfunction "VSSD2_66") (pintype "bidirectional"))
      (node (ref "U1") (pin "87") (pinfunction "VSSD3_87") (pintype "bidirectional"))
      (node (ref "U2") (pin "2") (pinfunction "GND_2") (pintype "input"))
      (node (ref "U3") (pin "2") (pinfunction "GND_2") (pintype "input"))
      (node (ref "U7") (pin "25") (pinfunction "VSSD1_25") (pintype "bidirectional"))
      (node (ref "U7") (pin "43") (pinfunction "VSSA_43") (pintype "bidirectional"))
      (node (ref "U7") (pin "45") (pinfunction "VSSD2_45") (pintype "bidirectional"))
      (node (ref "U7") (pin "5") (pinfunction "VSSB_5") (pintype "bidirectional"))
      (node (ref "U7") (pin "54") (pinfunction "P0[5]_54") (pintype "bidirectional"))
      (node (ref "U7") (pin "56") (pinfunction "P0[7]_56") (pintype "bidirectional"))
      (node (ref "U7") (pin "58") (pinfunction "VSSD3_58") (pintype "bidirectional"))
      (node (ref "U7") (pin "69") (pinfunction "VSSD0_69") (pintype "bidirectional"))
      (node (ref "U7") (pin "7") (pinfunction "VBOOST_7") (pintype "bidirectional"))
      (node (ref "U7") (pin "8") (pinfunction "VBAT_8") (pintype "bidirectional"))
      (node (ref "U7") (pin "9") (pinfunction "VSSD0_9") (pintype "bidirectional"))
    )
    (net (code "45") (name "Net-(C34-Pad1)") (class "Default")
      (node (ref "C34") (pin "1") (pinfunction "1_1") (pintype "passive"))
      (node (ref "SJ5") (pin "2") (pinfunction "2_2") (pintype "passive"))
    )
    (net (code "46") (name "Net-(C35-Pad1)") (class "Default")
      (node (ref "C35") (pin "1") (pinfunction "1_1") (pintype "passive"))
      (node (ref "SJ4") (pin "2") (pinfunction "2_2") (pintype "passive"))
    )
    (net (code "47") (name "Net-(C36-Pad1)") (class "Default")
      (node (ref "C36") (pin "1") (pinfunction "1_1") (pintype "passive"))
      (node (ref "SJ3") (pin "2") (pinfunction "2_2") (pintype "passive"))
    )
    (net (code "48") (name "Net-(D1-PadC)") (class "Default")
      (node (ref "D1") (pin "C") (pinfunction "C_C") (pintype "passive"))
      (node (ref "D2") (pin "C") (pinfunction "C_C") (pintype "passive"))
      (node (ref "D3") (pin "C") (pinfunction "C_C") (pintype "passive"))
      (node (ref "SJ1") (pin "1") (pinfunction "1_1") (pintype "passive"))
    )
    (net (code "49") (name "Net-(D3-PadA)") (class "Default")
      (node (ref "D3") (pin "A") (pinfunction "A_A") (pintype "passive"))
      (node (ref "JP18") (pin "PWR") (pinfunction "PWR_PWR") (pintype "bidirectional"))
    )
    (net (code "50") (name "Net-(D4-PadA)") (class "Default")
      (node (ref "D4") (pin "A") (pinfunction "A_A") (pintype "passive"))
      (node (ref "JP3") (pin "2") (pinfunction "2_2") (pintype "passive"))
      (node (ref "SJ2") (pin "1") (pinfunction "1_1") (pintype "passive"))
    )
    (net (code "51") (name "Net-(D5-PadA)") (class "Default")
      (node (ref "D5") (pin "A") (pinfunction "A_A") (pintype "passive"))
      (node (ref "R21") (pin "2") (pinfunction "2_2") (pintype "passive"))
    )
    (net (code "52") (name "Net-(D6-PadA)") (class "Default")
      (node (ref "D6") (pin "A") (pinfunction "A_A") (pintype "passive"))
      (node (ref "R20") (pin "2") (pinfunction "2_2") (pintype "passive"))
    )
    (net (code "53") (name "Net-(U1E-P15[6])") (class "Default")
      (node (ref "R16") (pin "1") (pinfunction "1_1") (pintype "passive"))
      (node (ref "U1") (pin "35") (pinfunction "P15[6]_35") (pintype "bidirectional"))
    )
    (net (code "54") (name "Net-(U1E-P15[7])") (class "Default")
      (node (ref "R17") (pin "1") (pinfunction "1_1") (pintype "passive"))
      (node (ref "U1") (pin "36") (pinfunction "P15[7]_36") (pintype "bidirectional"))
    )
    (net (code "55") (name "Net-(U1E-VCCA)") (class "Default")
      (node (ref "C1") (pin "1") (pinfunction "1_1") (pintype "passive"))
      (node (ref "U1") (pin "63") (pinfunction "VCCA_63") (pintype "bidirectional"))
    )
    (net (code "56") (name "Net-(U1E-VCCD0)") (class "Default")
      (node (ref "C7") (pin "1") (pinfunction "1_1") (pintype "passive"))
      (node (ref "U1") (pin "39") (pinfunction "VCCD0_39") (pintype "bidirectional"))
      (node (ref "U1") (pin "86") (pinfunction "VCCD1_86") (pintype "bidirectional"))
    )
    (net (code "57") (name "Net-(U2-BP)") (class "Default")
      (node (ref "C10") (pin "1") (pinfunction "1_1") (pintype "passive"))
      (node (ref "U2") (pin "4") (pinfunction "BP_4") (pintype "input"))
    )
    (net (code "58") (name "Net-(U3-BP)") (class "Default")
      (node (ref "C8") (pin "1") (pinfunction "1_1") (pintype "passive"))
      (node (ref "U3") (pin "4") (pinfunction "BP_4") (pintype "input"))
    )
    (net (code "59") (name "Net-(U7E-P15[6])") (class "Default")
      (node (ref "R18") (pin "1") (pinfunction "1_1") (pintype "passive"))
      (node (ref "U7") (pin "22") (pinfunction "P15[6]_22") (pintype "bidirectional"))
    )
    (net (code "60") (name "Net-(U7E-P15[7])") (class "Default")
      (node (ref "R19") (pin "1") (pinfunction "1_1") (pintype "passive"))
      (node (ref "U7") (pin "23") (pinfunction "P15[7]_23") (pintype "bidirectional"))
    )
    (net (code "61") (name "Net-(U7E-VCCA)") (class "Default")
      (node (ref "C17") (pin "1") (pinfunction "1_1") (pintype "passive"))
      (node (ref "U7") (pin "42") (pinfunction "VCCA_42") (pintype "bidirectional"))
    )
    (net (code "62") (name "Net-(U7E-VCCD0)") (class "Default")
      (node (ref "C16") (pin "1") (pinfunction "1_1") (pintype "passive"))
      (node (ref "U7") (pin "26") (pinfunction "VCCD0_26") (pintype "bidirectional"))
      (node (ref "U7") (pin "57") (pinfunction "VCCD1_57") (pintype "bidirectional"))
    )
    (net (code "63") (name "P0.0") (class "Default")
      (node (ref "JP8") (pin "1") (pinfunction "1_1") (pintype "passive"))
      (node (ref "U1") (pin "71") (pinfunction "P0[0]_71") (pintype "bidirectional"))
    )
    (net (code "64") (name "P0.1") (class "Default")
      (node (ref "JP8") (pin "2") (pinfunction "2_2") (pintype "passive"))
      (node (ref "U1") (pin "72") (pinfunction "P0[1]_72") (pintype "bidirectional"))
    )
    (net (code "65") (name "P0.2") (class "Default")
      (node (ref "JP8") (pin "3") (pinfunction "3_3") (pintype "passive"))
      (node (ref "SJ3") (pin "1") (pinfunction "1_1") (pintype "passive"))
      (node (ref "U1") (pin "73") (pinfunction "P0[2]_73") (pintype "bidirectional"))
    )
    (net (code "66") (name "P0.3") (class "Default")
      (node (ref "JP8") (pin "4") (pinfunction "4_4") (pintype "passive"))
      (node (ref "SJ4") (pin "1") (pinfunction "1_1") (pintype "passive"))
      (node (ref "U1") (pin "74") (pinfunction "P0[3]_74") (pintype "bidirectional"))
    )
    (net (code "67") (name "P0.4") (class "Default")
      (node (ref "JP8") (pin "5") (pinfunction "5_5") (pintype "passive"))
      (node (ref "SJ5") (pin "1") (pinfunction "1_1") (pintype "passive"))
      (node (ref "U1") (pin "76") (pinfunction "P0[4]_76") (pintype "bidirectional"))
    )
    (net (code "68") (name "P0.5") (class "Default")
      (node (ref "JP8") (pin "6") (pinfunction "6_6") (pintype "passive"))
      (node (ref "U1") (pin "77") (pinfunction "P0[5]_77") (pintype "bidirectional"))
    )
    (net (code "69") (name "P0.6") (class "Default")
      (node (ref "JP8") (pin "7") (pinfunction "7_7") (pintype "passive"))
      (node (ref "U1") (pin "78") (pinfunction "P0[6]_78") (pintype "bidirectional"))
    )
    (net (code "70") (name "P0.7") (class "Default")
      (node (ref "JP8") (pin "8") (pinfunction "8_8") (pintype "passive"))
      (node (ref "U1") (pin "79") (pinfunction "P0[7]_79") (pintype "bidirectional"))
    )
    (net (code "71") (name "P1.0") (class "Default")
      (node (ref "JP17") (pin "2") (pinfunction "2_2") (pintype "passive"))
      (node (ref "U1") (pin "20") (pinfunction "P1[0]_20") (pintype "bidirectional"))
      (node (ref "U7") (pin "46") (pinfunction "P12[2]_46") (pintype "bidirectional"))
    )
    (net (code "72") (name "P1.1") (class "Default")
      (node (ref "JP17") (pin "4") (pinfunction "4_4") (pintype "passive"))
      (node (ref "U1") (pin "21") (pinfunction "P1[1]_21") (pintype "bidirectional"))
      (node (ref "U7") (pin "47") (pinfunction "P12[3]_47") (pintype "bidirectional"))
    )
    (net (code "73") (name "P1.2") (class "Default")
      (node (ref "S6") (pin "1") (pinfunction "1_1") (pintype "passive"))
      (node (ref "U1") (pin "22") (pinfunction "P1[2]_22") (pintype "bidirectional"))
    )
    (net (code "74") (name "P1.3") (class "Default")
      (node (ref "JP17") (pin "6") (pinfunction "6_6") (pintype "passive"))
      (node (ref "U1") (pin "23") (pinfunction "P1[3]_23") (pintype "bidirectional"))
    )
    (net (code "75") (name "P1.4") (class "Default")
      (node (ref "JP17") (pin "8") (pinfunction "8_8") (pintype "passive"))
      (node (ref "U1") (pin "24") (pinfunction "P1[4]_24") (pintype "bidirectional"))
    )
    (net (code "76") (name "P3.0") (class "Default")
      (node (ref "JP12") (pin "1") (pinfunction "1_1") (pintype "passive"))
      (node (ref "U1") (pin "44") (pinfunction "P3[0]_44") (pintype "bidirectional"))
    )
    (net (code "77") (name "P3.1") (class "Default")
      (node (ref "JP12") (pin "2") (pinfunction "2_2") (pintype "passive"))
      (node (ref "U1") (pin "45") (pinfunction "P3[1]_45") (pintype "bidirectional"))
    )
    (net (code "78") (name "P3.2") (class "Default")
      (node (ref "JP12") (pin "3") (pinfunction "3_3") (pintype "passive"))
      (node (ref "U1") (pin "46") (pinfunction "P3[2]_46") (pintype "bidirectional"))
    )
    (net (code "79") (name "P3.3") (class "Default")
      (node (ref "JP12") (pin "4") (pinfunction "4_4") (pintype "passive"))
      (node (ref "U1") (pin "47") (pinfunction "P3[3]_47") (pintype "bidirectional"))
    )
    (net (code "80") (name "P3.4") (class "Default")
      (node (ref "JP12") (pin "5") (pinfunction "5_5") (pintype "passive"))
      (node (ref "U1") (pin "48") (pinfunction "P3[4]_48") (pintype "bidirectional"))
    )
    (net (code "81") (name "P3.5") (class "Default")
      (node (ref "JP12") (pin "6") (pinfunction "6_6") (pintype "passive"))
      (node (ref "U1") (pin "49") (pinfunction "P3[5]_49") (pintype "bidirectional"))
    )
    (net (code "82") (name "P3.6") (class "Default")
      (node (ref "JP12") (pin "7") (pinfunction "7_7") (pintype "passive"))
      (node (ref "U1") (pin "51") (pinfunction "P3[6]_51") (pintype "bidirectional"))
    )
    (net (code "83") (name "P3.7") (class "Default")
      (node (ref "JP12") (pin "8") (pinfunction "8_8") (pintype "passive"))
      (node (ref "U1") (pin "52") (pinfunction "P3[7]_52") (pintype "bidirectional"))
    )
    (net (code "84") (name "P4.0") (class "Default")
      (node (ref "JP9") (pin "2") (pinfunction "2_2") (pintype "passive"))
      (node (ref "U1") (pin "69") (pinfunction "P4[0]_69") (pintype "bidirectional"))
    )
    (net (code "85") (name "P4.1") (class "Default")
      (node (ref "JP9") (pin "1") (pinfunction "1_1") (pintype "passive"))
      (node (ref "U1") (pin "70") (pinfunction "P4[1]_70") (pintype "bidirectional"))
    )
    (net (code "86") (name "P4.2") (class "Default")
      (node (ref "JP9") (pin "4") (pinfunction "4_4") (pintype "passive"))
      (node (ref "U1") (pin "80") (pinfunction "P4[2]_80") (pintype "bidirectional"))
    )
    (net (code "87") (name "P4.3") (class "Default")
      (node (ref "JP9") (pin "3") (pinfunction "3_3") (pintype "passive"))
      (node (ref "U1") (pin "81") (pinfunction "P4[3]_81") (pintype "bidirectional"))
    )
    (net (code "88") (name "P4.4") (class "Default")
      (node (ref "JP9") (pin "6") (pinfunction "6_6") (pintype "passive"))
      (node (ref "U1") (pin "82") (pinfunction "P4[4]_82") (pintype "bidirectional"))
    )
    (net (code "89") (name "P4.5") (class "Default")
      (node (ref "JP9") (pin "5") (pinfunction "5_5") (pintype "passive"))
      (node (ref "U1") (pin "83") (pinfunction "P4[5]_83") (pintype "bidirectional"))
    )
    (net (code "90") (name "P4.6") (class "Default")
      (node (ref "JP9") (pin "8") (pinfunction "8_8") (pintype "passive"))
      (node (ref "U1") (pin "84") (pinfunction "P4[6]_84") (pintype "bidirectional"))
    )
    (net (code "91") (name "P4.7") (class "Default")
      (node (ref "JP9") (pin "7") (pinfunction "7_7") (pintype "passive"))
      (node (ref "U1") (pin "85") (pinfunction "P4[7]_85") (pintype "bidirectional"))
    )
    (net (code "92") (name "P5.0") (class "Default")
      (node (ref "JP11") (pin "2") (pinfunction "2_2") (pintype "passive"))
      (node (ref "U1") (pin "16") (pinfunction "P5[0]_16") (pintype "bidirectional"))
    )
    (net (code "93") (name "P5.1") (class "Default")
      (node (ref "JP11") (pin "1") (pinfunction "1_1") (pintype "passive"))
      (node (ref "U1") (pin "17") (pinfunction "P5[1]_17") (pintype "bidirectional"))
    )
    (net (code "94") (name "P5.2") (class "Default")
      (node (ref "JP11") (pin "4") (pinfunction "4_4") (pintype "passive"))
      (node (ref "U1") (pin "18") (pinfunction "P5[2]_18") (pintype "bidirectional"))
    )
    (net (code "95") (name "P5.3") (class "Default")
      (node (ref "JP11") (pin "3") (pinfunction "3_3") (pintype "passive"))
      (node (ref "U1") (pin "19") (pinfunction "P5[3]_19") (pintype "bidirectional"))
    )
    (net (code "96") (name "P5.4") (class "Default")
      (node (ref "JP11") (pin "6") (pinfunction "6_6") (pintype "passive"))
      (node (ref "U1") (pin "31") (pinfunction "P5[4]_31") (pintype "bidirectional"))
    )
    (net (code "97") (name "P5.5") (class "Default")
      (node (ref "JP11") (pin "5") (pinfunction "5_5") (pintype "passive"))
      (node (ref "U1") (pin "32") (pinfunction "P5[5]_32") (pintype "bidirectional"))
    )
    (net (code "98") (name "P5.6") (class "Default")
      (node (ref "JP11") (pin "8") (pinfunction "8_8") (pintype "passive"))
      (node (ref "U1") (pin "33") (pinfunction "P5[6]_33") (pintype "bidirectional"))
    )
    (net (code "99") (name "P5.7") (class "Default")
      (node (ref "JP11") (pin "7") (pinfunction "7_7") (pintype "passive"))
      (node (ref "U1") (pin "34") (pinfunction "P5[7]_34") (pintype "bidirectional"))
    )
    (net (code "100") (name "P12.0") (class "Default")
      (node (ref "JP10") (pin "3") (pinfunction "3_3") (pintype "passive"))
      (node (ref "U1") (pin "53") (pinfunction "P12[0]_53") (pintype "bidirectional"))
    )
    (net (code "101") (name "P12.1") (class "Default")
      (node (ref "JP10") (pin "4") (pinfunction "4_4") (pintype "passive"))
      (node (ref "U1") (pin "54") (pinfunction "P12[1]_54") (pintype "bidirectional"))
    )
    (net (code "102") (name "P12.2") (class "Default")
      (node (ref "JP10") (pin "5") (pinfunction "5_5") (pintype "passive"))
      (node (ref "U1") (pin "67") (pinfunction "P12[2]_67") (pintype "bidirectional"))
    )
    (net (code "103") (name "P12.3") (class "Default")
      (node (ref "JP10") (pin "6") (pinfunction "6_6") (pintype "passive"))
      (node (ref "U1") (pin "68") (pinfunction "P12[3]_68") (pintype "bidirectional"))
    )
    (net (code "104") (name "P12.6") (class "Default")
      (node (ref "JP10") (pin "7") (pinfunction "7_7") (pintype "passive"))
      (node (ref "U1") (pin "29") (pinfunction "P12[6]_29") (pintype "bidirectional"))
    )
    (net (code "105") (name "P12.7") (class "Default")
      (node (ref "JP10") (pin "8") (pinfunction "8_8") (pintype "passive"))
      (node (ref "U1") (pin "30") (pinfunction "P12[7]_30") (pintype "bidirectional"))
    )
    (net (code "106") (name "P15.0") (class "Default")
      (node (ref "C14") (pin "1") (pinfunction "1_1") (pintype "passive"))
      (node (ref "U1") (pin "42") (pinfunction "P15[0]_42") (pintype "bidirectional"))
      (node (ref "Y2") (pin "1") (pinfunction "1_1") (pintype "passive"))
    )
    (net (code "107") (name "P15.1") (class "Default")
      (node (ref "C12") (pin "1") (pinfunction "1_1") (pintype "passive"))
      (node (ref "U1") (pin "43") (pinfunction "P15[1]_43") (pintype "bidirectional"))
      (node (ref "Y2") (pin "2") (pinfunction "2_2") (pintype "passive"))
    )
    (net (code "108") (name "P15.2") (class "Default")
      (node (ref "C18") (pin "1") (pinfunction "1_1") (pintype "passive"))
      (node (ref "U1") (pin "55") (pinfunction "P15[2]_55") (pintype "bidirectional"))
      (node (ref "Y1") (pin "2") (pinfunction "2_2") (pintype "passive"))
    )
    (net (code "109") (name "P15.3") (class "Default")
      (node (ref "C24") (pin "1") (pinfunction "1_1") (pintype "passive"))
      (node (ref "U1") (pin "56") (pinfunction "P15[3]_56") (pintype "bidirectional"))
      (node (ref "Y1") (pin "1") (pinfunction "1_1") (pintype "passive"))
    )
    (net (code "110") (name "PSOC_D+_BUS") (class "Default")
      (node (ref "JP1") (pin "D+1") (pinfunction "D+_D+1") (pintype "bidirectional"))
      (node (ref "R16") (pin "2") (pinfunction "2_2") (pintype "passive"))
    )
    (net (code "111") (name "PSOC_D-_BUS") (class "Default")
      (node (ref "JP1") (pin "D-1") (pinfunction "D-_D-1") (pintype "bidirectional"))
      (node (ref "R17") (pin "2") (pinfunction "2_2") (pintype "passive"))
    )
    (net (code "112") (name "VDDIO") (class "Default")
      (node (ref "C13") (pin "1") (pinfunction "1_1") (pintype "passive"))
      (node (ref "C15") (pin "1") (pinfunction "1_1") (pintype "passive"))
      (node (ref "C25") (pin "1") (pinfunction "1_1") (pintype "passive"))
      (node (ref "C27") (pin "1") (pinfunction "1_1") (pintype "passive"))
      (node (ref "C29") (pin "1") (pinfunction "1_1") (pintype "passive"))
      (node (ref "C31") (pin "1") (pinfunction "1_1") (pintype "passive"))
      (node (ref "C9") (pin "1") (pinfunction "1_1") (pintype "passive"))
      (node (ref "JP10") (pin "2") (pinfunction "2_2") (pintype "passive"))
      (node (ref "JP11") (pin "10") (pinfunction "10_10") (pintype "passive"))
      (node (ref "JP11") (pin "9") (pinfunction "9_9") (pintype "passive"))
      (node (ref "JP12") (pin "10") (pinfunction "10_10") (pintype "passive"))
      (node (ref "JP12") (pin "9") (pinfunction "9_9") (pintype "passive"))
      (node (ref "JP14") (pin "1") (pinfunction "1_1") (pintype "passive"))
      (node (ref "JP15") (pin "1") (pinfunction "1_1") (pintype "passive"))
      (node (ref "JP17") (pin "1") (pinfunction "1_1") (pintype "passive"))
      (node (ref "JP8") (pin "10") (pinfunction "10_10") (pintype "passive"))
      (node (ref "JP8") (pin "9") (pinfunction "9_9") (pintype "passive"))
      (node (ref "JP9") (pin "10") (pinfunction "10_10") (pintype "passive"))
      (node (ref "JP9") (pin "9") (pinfunction "9_9") (pintype "passive"))
      (node (ref "S4") (pin "2") (pinfunction "P_2") (pintype "passive"))
      (node (ref "U1") (pin "26") (pinfunction "VDDIO1_26") (pintype "bidirectional"))
      (node (ref "U1") (pin "50") (pinfunction "VDDIO3_50") (pintype "bidirectional"))
      (node (ref "U1") (pin "75") (pinfunction "VDDIO0_75") (pintype "bidirectional"))
      (node (ref "U7") (pin "17") (pinfunction "VDDIO1_17") (pintype "bidirectional"))
      (node (ref "U7") (pin "35") (pinfunction "VDDIO3_35") (pintype "bidirectional"))
      (node (ref "U7") (pin "52") (pinfunction "VDDIO0_52") (pintype "bidirectional"))
      (node (ref "U7") (pin "67") (pinfunction "VDDIO2_67") (pintype "bidirectional"))
    )
    (net (code "113") (name "VDDIO_ARDUINO") (class "Default")
      (node (ref "C11") (pin "1") (pinfunction "1_1") (pintype "passive"))
      (node (ref "JP13") (pin "2") (pinfunction "2_2") (pintype "bidirectional"))
      (node (ref "JP6") (pin "7") (pinfunction "7_7") (pintype "passive"))
      (node (ref "S3") (pin "2") (pinfunction "P_2") (pintype "passive"))
      (node (ref "U1") (pin "100") (pinfunction "VDDIO2_100") (pintype "bidirectional"))
    )
    (net (code "114") (name "V_BUS_DEBUG") (class "Default")
      (node (ref "R4") (pin "2") (pinfunction "2_2") (pintype "passive"))
      (node (ref "R5") (pin "2") (pinfunction "2_2") (pintype "passive"))
      (node (ref "U7") (pin "18") (pinfunction "P1[6]_18") (pintype "bidirectional"))
    )
    (net (code "115") (name "V_BUS_HOST") (class "Default")
      (node (ref "R3") (pin "2") (pinfunction "2_2") (pintype "passive"))
      (node (ref "R6") (pin "2") (pinfunction "2_2") (pintype "passive"))
      (node (ref "U1") (pin "27") (pinfunction "P1[6]_27") (pintype "bidirectional"))
    )
    (net (code "116") (name "V_DEBUG") (class "Default")
      (node (ref "D2") (pin "A") (pinfunction "A_A") (pintype "passive"))
      (node (ref "JP2") (pin "VBUS1") (pinfunction "VCC_VBUS1") (pintype "bidirectional"))
      (node (ref "R4") (pin "1") (pinfunction "1_1") (pintype "passive"))
    )
    (net (code "117") (name "V_HOST") (class "Default")
      (node (ref "D1") (pin "A") (pinfunction "A_A") (pintype "passive"))
      (node (ref "JP1") (pin "VBUS1") (pinfunction "VCC_VBUS1") (pintype "bidirectional"))
      (node (ref "R3") (pin "1") (pinfunction "1_1") (pintype "passive"))
    )
    (net (code "118") (name "V_IN") (class "Default")
      (node (ref "D4") (pin "C") (pinfunction "C_C") (pintype "passive"))
      (node (ref "JP6") (pin "1") (pinfunction "1_1") (pintype "passive"))
      (node (ref "SJ1") (pin "2") (pinfunction "2_2") (pintype "passive"))
      (node (ref "SJ2") (pin "2") (pinfunction "2_2") (pintype "passive"))
      (node (ref "U2") (pin "1") (pinfunction "IN_1") (pintype "input"))
      (node (ref "U2") (pin "3") (pinfunction "EN_3") (pintype "input"))
      (node (ref "U3") (pin "1") (pinfunction "IN_1") (pintype "input"))
      (node (ref "U3") (pin "3") (pinfunction "EN_3") (pintype "input"))
    )
    (net (code "119") (name "unconnected-(JP1-ID-PadID1)") (class "Default")
      (node (ref "JP1") (pin "ID1") (pinfunction "ID_ID1") (pintype "bidirectional"))
    )
    (net (code "120") (name "unconnected-(JP2-ID-PadID1)") (class "Default")
      (node (ref "JP2") (pin "ID1") (pinfunction "ID_ID1") (pintype "bidirectional"))
    )
    (net (code "121") (name "unconnected-(JP6-Pad8)") (class "Default")
      (node (ref "JP6") (pin "8") (pinfunction "8_8") (pintype "passive"))
    )
    (net (code "122") (name "unconnected-(JP7-Pad8)") (class "Default")
      (node (ref "JP7") (pin "8") (pinfunction "8_8") (pintype "passive"))
    )
    (net (code "123") (name "unconnected-(U1B-P1[5]-Pad25)") (class "Default")
      (node (ref "U1") (pin "25") (pinfunction "P1[5]_25") (pintype "bidirectional"))
    )
    (net (code "124") (name "unconnected-(U1B-P1[7]-Pad28)") (class "Default")
      (node (ref "U1") (pin "28") (pinfunction "P1[7]_28") (pintype "bidirectional"))
    )
    (net (code "125") (name "unconnected-(U1E-IND-Pad11)") (class "Default")
      (node (ref "U1") (pin "11") (pinfunction "IND_11") (pintype "bidirectional"))
    )
    (net (code "126") (name "unconnected-(U7A-P0[6]-Pad55)") (class "Default")
      (node (ref "U7") (pin "55") (pinfunction "P0[6]_55") (pintype "bidirectional"))
    )
    (net (code "127") (name "unconnected-(U7B-P1[5]-Pad16)") (class "Default")
      (node (ref "U7") (pin "16") (pinfunction "P1[5]_16") (pintype "bidirectional"))
    )
    (net (code "128") (name "unconnected-(U7B-P1[7]-Pad19)") (class "Default")
      (node (ref "U7") (pin "19") (pinfunction "P1[7]_19") (pintype "bidirectional"))
    )
    (net (code "129") (name "unconnected-(U7C-P2[0]-Pad62)") (class "Default")
      (node (ref "U7") (pin "62") (pinfunction "P2[0]_62") (pintype "bidirectional"))
    )
    (net (code "130") (name "unconnected-(U7C-P2[1]-Pad63)") (class "Default")
      (node (ref "U7") (pin "63") (pinfunction "P2[1]_63") (pintype "bidirectional"))
    )
    (net (code "131") (name "unconnected-(U7C-P2[3]-Pad65)") (class "Default")
      (node (ref "U7") (pin "65") (pinfunction "P2[3]_65") (pintype "bidirectional"))
    )
    (net (code "132") (name "unconnected-(U7C-P2[4]-Pad66)") (class "Default")
      (node (ref "U7") (pin "66") (pinfunction "P2[4]_66") (pintype "bidirectional"))
    )
    (net (code "133") (name "unconnected-(U7C-P2[5]-Pad68)") (class "Default")
      (node (ref "U7") (pin "68") (pinfunction "P2[5]_68") (pintype "bidirectional"))
    )
    (net (code "134") (name "unconnected-(U7C-P2[6]-Pad1)") (class "Default")
      (node (ref "U7") (pin "1") (pinfunction "P2[6]_1") (pintype "bidirectional"))
    )
    (net (code "135") (name "unconnected-(U7C-P2[7]-Pad2)") (class "Default")
      (node (ref "U7") (pin "2") (pinfunction "P2[7]_2") (pintype "bidirectional"))
    )
    (net (code "136") (name "unconnected-(U7C-P12[5]-Pad4)") (class "Default")
      (node (ref "U7") (pin "4") (pinfunction "P12[5]_4") (pintype "bidirectional"))
    )
    (net (code "137") (name "unconnected-(U7C-P15[4]-Pad60)") (class "Default")
      (node (ref "U7") (pin "60") (pinfunction "P15[4]_60") (pintype "bidirectional"))
    )
    (net (code "138") (name "unconnected-(U7C-P15[5]-Pad61)") (class "Default")
      (node (ref "U7") (pin "61") (pinfunction "P15[5]_61") (pintype "bidirectional"))
    )
    (net (code "139") (name "unconnected-(U7D-P3[2]-Pad31)") (class "Default")
      (node (ref "U7") (pin "31") (pinfunction "P3[2]_31") (pintype "bidirectional"))
    )
    (net (code "140") (name "unconnected-(U7D-P3[3]-Pad32)") (class "Default")
      (node (ref "U7") (pin "32") (pinfunction "P3[3]_32") (pintype "bidirectional"))
    )
    (net (code "141") (name "unconnected-(U7D-P12[0]-Pad38)") (class "Default")
      (node (ref "U7") (pin "38") (pinfunction "P12[0]_38") (pintype "bidirectional"))
    )
    (net (code "142") (name "unconnected-(U7D-P12[1]-Pad39)") (class "Default")
      (node (ref "U7") (pin "39") (pinfunction "P12[1]_39") (pintype "bidirectional"))
    )
    (net (code "143") (name "unconnected-(U7D-P15[0]-Pad27)") (class "Default")
      (node (ref "U7") (pin "27") (pinfunction "P15[0]_27") (pintype "bidirectional"))
    )
    (net (code "144") (name "unconnected-(U7D-P15[1]-Pad28)") (class "Default")
      (node (ref "U7") (pin "28") (pinfunction "P15[1]_28") (pintype "bidirectional"))
    )
    (net (code "145") (name "unconnected-(U7D-P15[2]-Pad40)") (class "Default")
      (node (ref "U7") (pin "40") (pinfunction "P15[2]_40") (pintype "bidirectional"))
    )
    (net (code "146") (name "unconnected-(U7D-P15[3]-Pad41)") (class "Default")
      (node (ref "U7") (pin "41") (pinfunction "P15[3]_41") (pintype "bidirectional"))
    )
    (net (code "147") (name "unconnected-(U7E-IND-Pad6)") (class "Default")
      (node (ref "U7") (pin "6") (pinfunction "IND_6") (pintype "bidirectional"))
    )
    (net (code "148") (name "~{DEBUG_RESET}") (class "Default")
      (node (ref "C38") (pin "1") (pinfunction "1_1") (pintype "passive"))
      (node (ref "JP14") (pin "10") (pinfunction "10_10") (pintype "passive"))
      (node (ref "R2") (pin "1") (pinfunction "1_1") (pintype "passive"))
      (node (ref "S1") (pin "1") (pinfunction "1_1") (pintype "passive"))
      (node (ref "U7") (pin "10") (pinfunction "~{XRES}_10") (pintype "bidirectional"))
    )
    (net (code "149") (name "~{RESET}") (class "Default")
      (node (ref "C37") (pin "1") (pinfunction "1_1") (pintype "passive"))
      (node (ref "JP13") (pin "5") (pinfunction "5_5") (pintype "bidirectional"))
      (node (ref "JP17") (pin "10") (pinfunction "10_10") (pintype "passive"))
      (node (ref "JP6") (pin "6") (pinfunction "6_6") (pintype "passive"))
      (node (ref "R1") (pin "1") (pinfunction "1_1") (pintype "passive"))
      (node (ref "S2") (pin "1") (pinfunction "1_1") (pintype "passive"))
      (node (ref "U1") (pin "15") (pinfunction "~{XRES}_15") (pintype "bidirectional"))
      (node (ref "U7") (pin "3") (pinfunction "P12[4]_3") (pintype "bidirectional"))
    )
  )
)
